# DriveBoard.net
KiCad netlist of a schematic drawn in Altium Designer
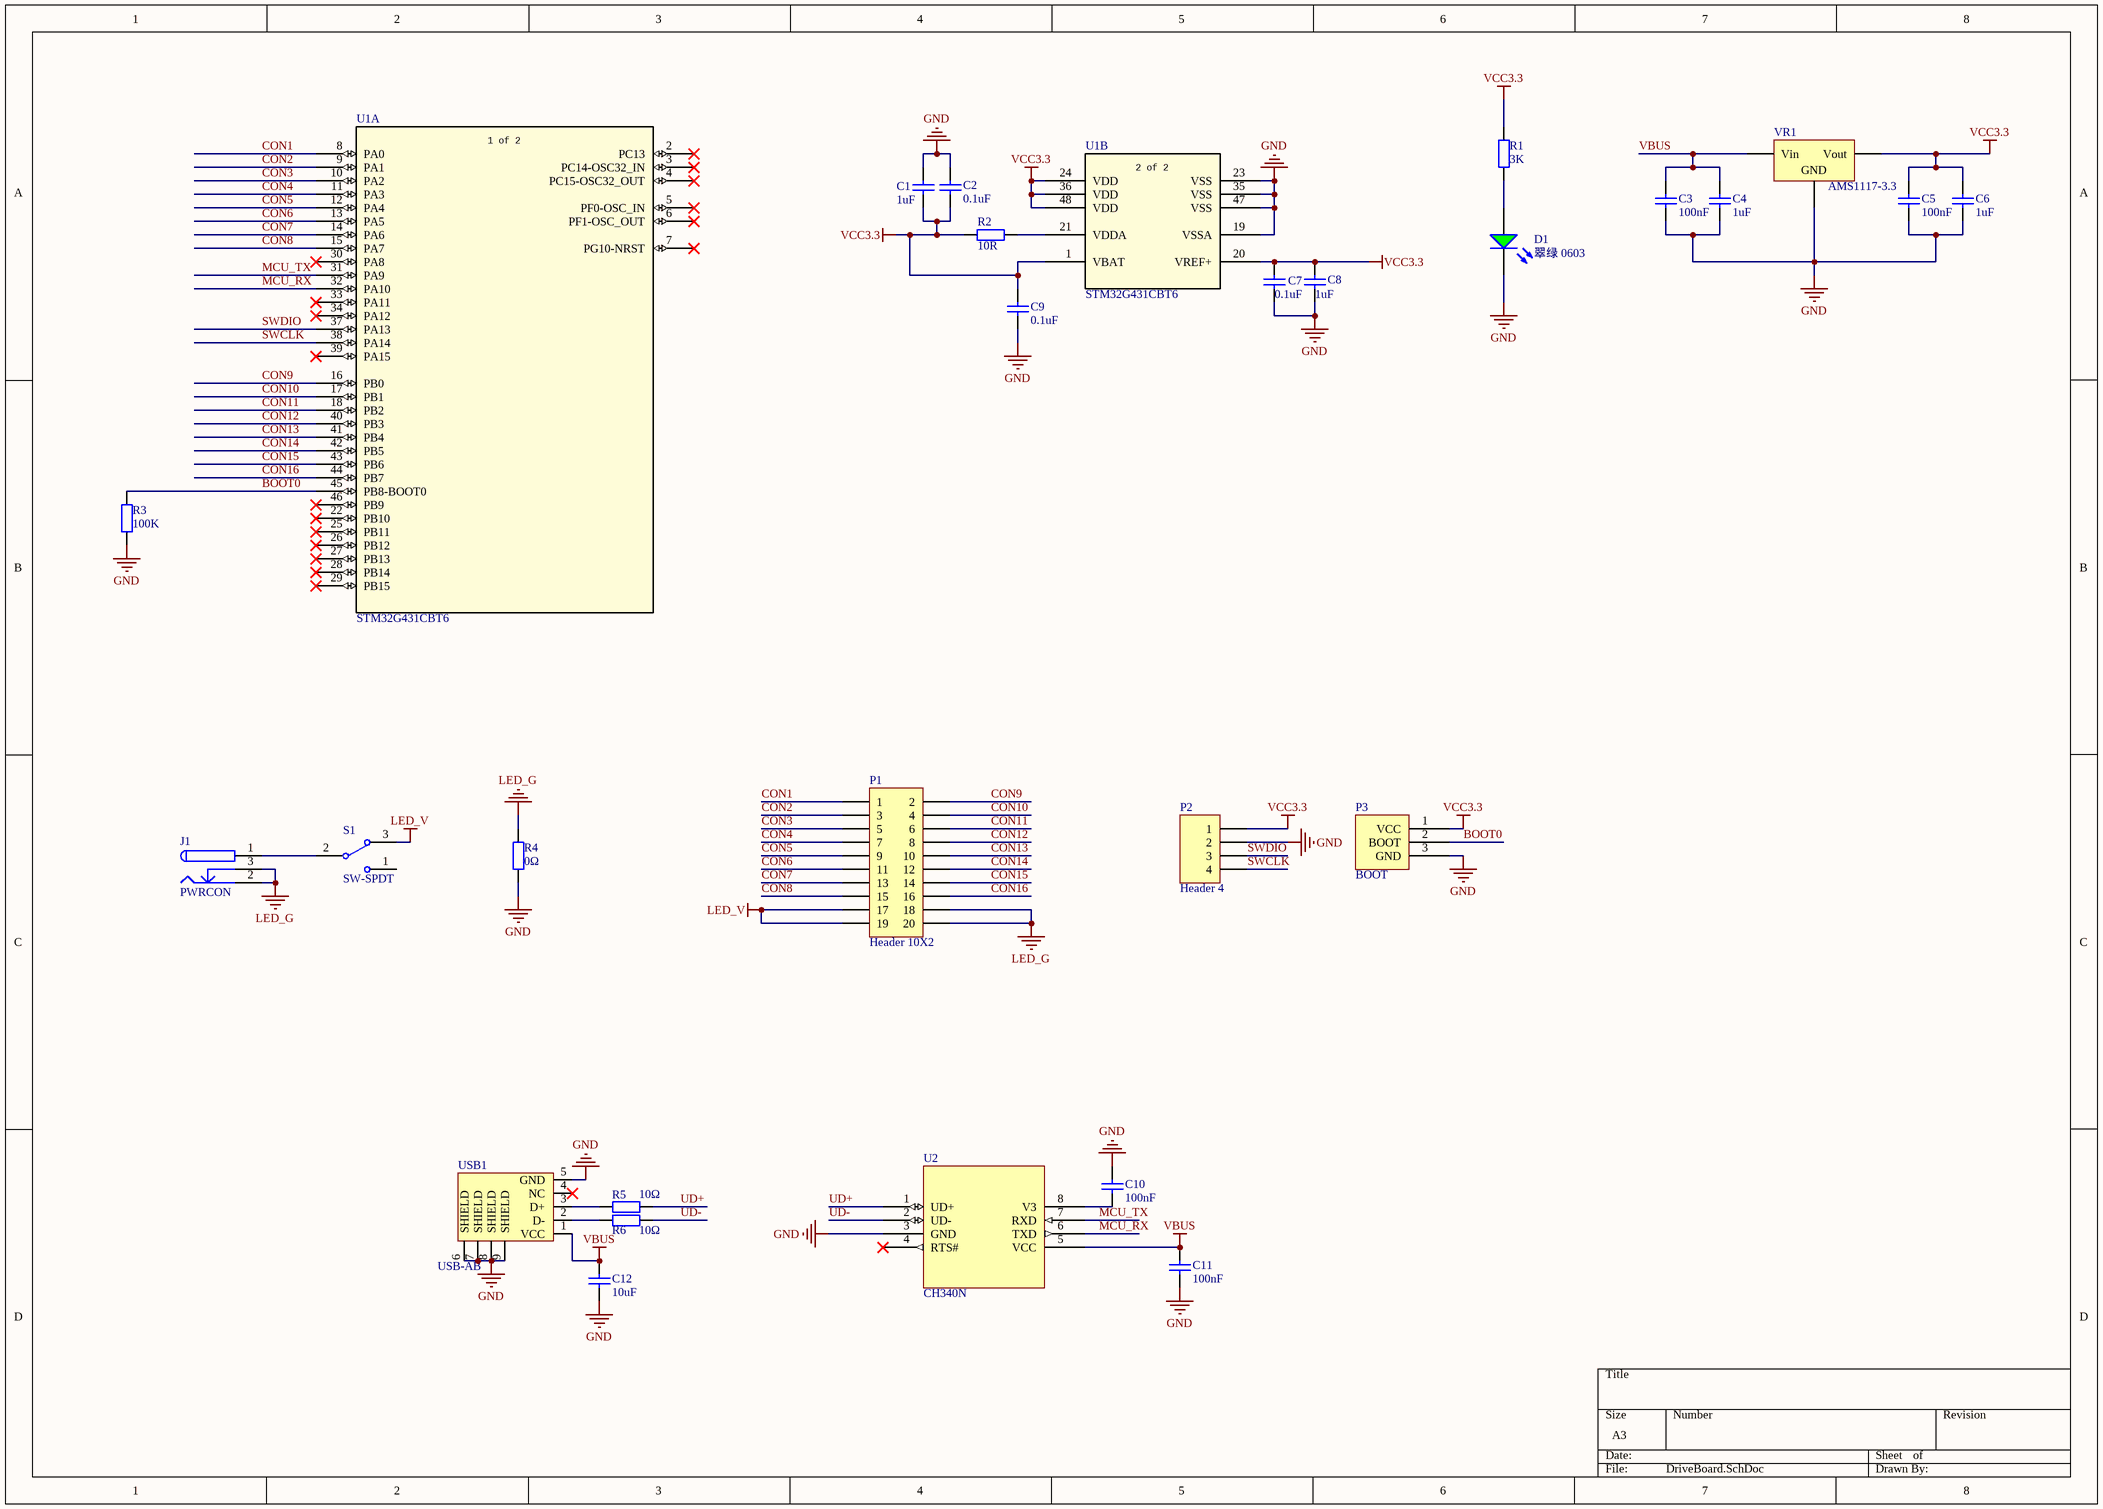
[diagram p0: DriveBoard.SchDoc]

(export (version "E")
  (design (tool "Eeschema 10.0.6"))
  (components
    (comp (ref "C1")
      (value "1uF")
      (footprint "0603_C")
      (description "贴片电容")
      (libsource (lib "Miscellaneous Devices LC") (part "0805 1uF (105) 10% 50V"))
    )
    (comp (ref "C2")
      (value "0.1uF")
      (footprint "0603_C")
      (description "贴片电容")
      (libsource (lib "Miscellaneous Devices LC") (part "0805 1uF (105) 10% 50V"))
    )
    (comp (ref "C3")
      (value "100nF")
      (footprint "0603_C")
      (description "贴片电容")
      (libsource (lib "Miscellaneous Devices LC") (part "0603 100nF (104) 10% 50V"))
    )
    (comp (ref "C4")
      (value "1uF")
      (footprint "0603_C")
      (description "贴片电容")
      (libsource (lib "Miscellaneous Devices LC") (part "0603 1uF (105) 10% 50V"))
    )
    (comp (ref "C5")
      (value "100nF")
      (footprint "0603_C")
      (description "贴片电容")
      (libsource (lib "Miscellaneous Devices LC") (part "0603 100nF (104) 10% 50V"))
    )
    (comp (ref "C6")
      (value "1uF")
      (footprint "0603_C")
      (description "贴片电容")
      (libsource (lib "Miscellaneous Devices LC") (part "0603 1uF (105) 10% 50V"))
    )
    (comp (ref "C7")
      (value "0.1uF")
      (footprint "0603_C")
      (description "贴片电容")
      (libsource (lib "Miscellaneous Devices LC") (part "0805 1uF (105) 10% 50V"))
    )
    (comp (ref "C8")
      (value "1uF")
      (footprint "0603_C")
      (description "贴片电容")
      (libsource (lib "Miscellaneous Devices LC") (part "0805 1uF (105) 10% 50V"))
    )
    (comp (ref "C9")
      (value "0.1uF")
      (footprint "0603_C")
      (description "贴片电容")
      (libsource (lib "Miscellaneous Devices LC") (part "0805 1uF (105) 10% 50V"))
    )
    (comp (ref "C10")
      (value "100nF")
      (footprint "0603_C")
      (description "贴片电容")
      (libsource (lib "Miscellaneous Devices LC") (part "0603 100nF (104) 10% 50V"))
    )
    (comp (ref "C11")
      (value "100nF")
      (footprint "0603_C")
      (description "贴片电容")
      (libsource (lib "Miscellaneous Devices LC") (part "0603 100nF (104) 10% 50V"))
    )
    (comp (ref "C12")
      (value "10uF")
      (footprint "0603_C")
      (description "贴片电容")
      (libsource (lib "Miscellaneous Devices LC") (part "0603 100nF (104) 10% 50V"))
    )
    (comp (ref "D1")
      (value "翠绿 0603")
      (footprint "0603_LED_S1")
      (description "发光二极管")
      (libsource (lib "Miscellaneous Devices LC") (part "0805 翠绿"))
    )
    (comp (ref "J1")
      (value "PWRCON")
      (footprint "Connetor:DC-005")
      (description "直流电源端子")
      (fields (field (name "PUBLISHER") "Altium Limited"))
      (libsource (lib "myself") (part "PWRCON"))
    )
    (comp (ref "P1")
      (value "Header 10X2")
      (footprint "HDR2.54-M-LS-2x10P")
      (description "Header, 10-Pin, Dual row")
      (fields (field (name "PUBLISHER") "Altium Limited"))
      (libsource (lib "Miscellaneous Connectors") (part "Header 10X2"))
    )
    (comp (ref "P2")
      (value "Header 4")
      (footprint "HDR1X4")
      (description "Header, 4-Pin")
      (fields (field (name "PUBLISHER") "Altium Limited"))
      (libsource (lib "Miscellaneous Connectors") (part "Header 4"))
    )
    (comp (ref "P3") (value "BOOT") (footprint "BOOT") (libsource (lib "myself") (part "BOOT")))
    (comp (ref "R1")
      (value "3K")
      (footprint "0603_R")
      (description "贴片电阻")
      (libsource (lib "Miscellaneous Devices LC") (part "0805 9.1KΩ (9101) 1%"))
    )
    (comp (ref "R2")
      (value "10R")
      (footprint "0603_R")
      (description "贴片电阻")
      (libsource (lib "Miscellaneous Devices LC") (part "0805 9.1KΩ (9101) 1%"))
    )
    (comp (ref "R3")
      (value "100K")
      (footprint "0603_R")
      (description "贴片电阻")
      (libsource (lib "") (part "0805 9.1KΩ (9101) 1%_1"))
    )
    (comp (ref "R4")
      (value "0Ω")
      (footprint "LC-0603_R")
      (description "贴片电阻")
      (libsource (lib "sfzself") (part "0603 0Ω (0R0) 1%"))
    )
    (comp (ref "R5")
      (value "10Ω")
      (footprint "0603_R")
      (description "贴片电阻")
      (libsource (lib "Miscellaneous Devices LC") (part "0603 10Ω (10R0) 1%"))
    )
    (comp (ref "R6")
      (value "10Ω")
      (footprint "0603_R")
      (description "贴片电阻")
      (libsource (lib "Miscellaneous Devices LC") (part "0603 10Ω (10R0) 1%"))
    )
    (comp (ref "S1")
      (value "SW-SPDT")
      (footprint "SWITCH_A1")
      (description "开关")
      (fields (field (name "PUBLISHER") "Altium Limited"))
      (libsource (lib "Fszhang") (part "SW-SPDT"))
    )
    (comp (ref "U1")
      (value "STM32G431CBT6")
      (footprint "LQFP48-7x7mm")
      (description "No Description Available")
      (fields (field (name "COPYRIGHT") "Copyright (C) 2018 Accelerated Designs. All rights reserved"))
      (libsource (lib "myself") (part "STM32G431CBT6"))
    )
    (comp (ref "U2")
      (value "CH340N")
      (footprint "SOP8")
      (description "USB to TTL Serial / UART")
      (libsource (lib "myself") (part "CH340N"))
    )
    (comp (ref "USB1")
      (value "USB-AB")
      (footprint "USB_AB - 5S - B")
      (description "MicroUSB")
      (libsource (lib "myself") (part "USB-AB"))
    )
    (comp (ref "VR1")
      (value "AMS1117-3.3")
      (footprint "SOT-223")
      (description "低压差线性稳压(LDO)")
      (libsource (lib "Miscellaneous Devices LC") (part "SOT-223 AMS1117-3.3"))
    )
  )
  (nets
    (net (code "1") (name "/BOOT0") (class "Default")
      (node (ref "P3") (pin "2") (pinfunction "BOOT_2") (pintype "passive"))
      (node (ref "R3") (pin "1") (pinfunction "1_1") (pintype "passive"))
      (node (ref "U1") (pin "45") (pinfunction "PB8-BOOT0_45") (pintype "bidirectional"))
    )
    (net (code "2") (name "/CON1") (class "Default")
      (node (ref "P1") (pin "1") (pinfunction "1_1") (pintype "passive"))
      (node (ref "U1") (pin "8") (pinfunction "PA0_8") (pintype "bidirectional"))
    )
    (net (code "3") (name "/CON2") (class "Default")
      (node (ref "P1") (pin "3") (pinfunction "3_3") (pintype "passive"))
      (node (ref "U1") (pin "9") (pinfunction "PA1_9") (pintype "bidirectional"))
    )
    (net (code "4") (name "/CON3") (class "Default")
      (node (ref "P1") (pin "5") (pinfunction "5_5") (pintype "passive"))
      (node (ref "U1") (pin "10") (pinfunction "PA2_10") (pintype "bidirectional"))
    )
    (net (code "5") (name "/CON4") (class "Default")
      (node (ref "P1") (pin "7") (pinfunction "7_7") (pintype "passive"))
      (node (ref "U1") (pin "11") (pinfunction "PA3_11") (pintype "bidirectional"))
    )
    (net (code "6") (name "/CON5") (class "Default")
      (node (ref "P1") (pin "9") (pinfunction "9_9") (pintype "passive"))
      (node (ref "U1") (pin "12") (pinfunction "PA4_12") (pintype "bidirectional"))
    )
    (net (code "7") (name "/CON6") (class "Default")
      (node (ref "P1") (pin "11") (pinfunction "11_11") (pintype "passive"))
      (node (ref "U1") (pin "13") (pinfunction "PA5_13") (pintype "bidirectional"))
    )
    (net (code "8") (name "/CON7") (class "Default")
      (node (ref "P1") (pin "13") (pinfunction "13_13") (pintype "passive"))
      (node (ref "U1") (pin "14") (pinfunction "PA6_14") (pintype "bidirectional"))
    )
    (net (code "9") (name "/CON8") (class "Default")
      (node (ref "P1") (pin "15") (pinfunction "15_15") (pintype "passive"))
      (node (ref "U1") (pin "15") (pinfunction "PA7_15") (pintype "bidirectional"))
    )
    (net (code "10") (name "/CON9") (class "Default")
      (node (ref "P1") (pin "2") (pinfunction "2_2") (pintype "passive"))
      (node (ref "U1") (pin "16") (pinfunction "PB0_16") (pintype "bidirectional"))
    )
    (net (code "11") (name "/CON10") (class "Default")
      (node (ref "P1") (pin "4") (pinfunction "4_4") (pintype "passive"))
      (node (ref "U1") (pin "17") (pinfunction "PB1_17") (pintype "bidirectional"))
    )
    (net (code "12") (name "/CON11") (class "Default")
      (node (ref "P1") (pin "6") (pinfunction "6_6") (pintype "passive"))
      (node (ref "U1") (pin "18") (pinfunction "PB2_18") (pintype "bidirectional"))
    )
    (net (code "13") (name "/CON12") (class "Default")
      (node (ref "P1") (pin "8") (pinfunction "8_8") (pintype "passive"))
      (node (ref "U1") (pin "40") (pinfunction "PB3_40") (pintype "bidirectional"))
    )
    (net (code "14") (name "/CON13") (class "Default")
      (node (ref "P1") (pin "10") (pinfunction "10_10") (pintype "passive"))
      (node (ref "U1") (pin "41") (pinfunction "PB4_41") (pintype "bidirectional"))
    )
    (net (code "15") (name "/CON14") (class "Default")
      (node (ref "P1") (pin "12") (pinfunction "12_12") (pintype "passive"))
      (node (ref "U1") (pin "42") (pinfunction "PB5_42") (pintype "bidirectional"))
    )
    (net (code "16") (name "/CON15") (class "Default")
      (node (ref "P1") (pin "14") (pinfunction "14_14") (pintype "passive"))
      (node (ref "U1") (pin "43") (pinfunction "PB6_43") (pintype "bidirectional"))
    )
    (net (code "17") (name "/CON16") (class "Default")
      (node (ref "P1") (pin "16") (pinfunction "16_16") (pintype "passive"))
      (node (ref "U1") (pin "44") (pinfunction "PB7_44") (pintype "bidirectional"))
    )
    (net (code "18") (name "/MCU_RX") (class "Default")
      (node (ref "U1") (pin "32") (pinfunction "PA10_32") (pintype "bidirectional"))
      (node (ref "U2") (pin "6") (pinfunction "TXD_6") (pintype "output"))
    )
    (net (code "19") (name "/MCU_TX") (class "Default")
      (node (ref "U1") (pin "31") (pinfunction "PA9_31") (pintype "bidirectional"))
      (node (ref "U2") (pin "7") (pinfunction "RXD_7") (pintype "input"))
    )
    (net (code "20") (name "/SWCLK") (class "Default")
      (node (ref "P2") (pin "4") (pinfunction "4_4") (pintype "passive"))
      (node (ref "U1") (pin "38") (pinfunction "PA14_38") (pintype "bidirectional"))
    )
    (net (code "21") (name "/SWDIO") (class "Default")
      (node (ref "P2") (pin "3") (pinfunction "3_3") (pintype "passive"))
      (node (ref "U1") (pin "37") (pinfunction "PA13_37") (pintype "bidirectional"))
    )
    (net (code "22") (name "/UD+") (class "Default")
      (node (ref "R5") (pin "2") (pinfunction "2_2") (pintype "passive"))
      (node (ref "U2") (pin "1") (pinfunction "UD+_1") (pintype "bidirectional"))
    )
    (net (code "23") (name "/UD-") (class "Default")
      (node (ref "R6") (pin "2") (pinfunction "2_2") (pintype "passive"))
      (node (ref "U2") (pin "2") (pinfunction "UD-_2") (pintype "bidirectional"))
    )
    (net (code "24") (name "GND") (class "Default")
      (node (ref "C1") (pin "1") (pinfunction "1_1") (pintype "passive"))
      (node (ref "C10") (pin "2") (pinfunction "2_2") (pintype "passive"))
      (node (ref "C11") (pin "1") (pinfunction "1_1") (pintype "passive"))
      (node (ref "C12") (pin "1") (pinfunction "1_1") (pintype "passive"))
      (node (ref "C2") (pin "1") (pinfunction "1_1") (pintype "passive"))
      (node (ref "C3") (pin "1") (pinfunction "1_1") (pintype "passive"))
      (node (ref "C4") (pin "1") (pinfunction "1_1") (pintype "passive"))
      (node (ref "C5") (pin "1") (pinfunction "1_1") (pintype "passive"))
      (node (ref "C6") (pin "1") (pinfunction "1_1") (pintype "passive"))
      (node (ref "C7") (pin "1") (pinfunction "1_1") (pintype "passive"))
      (node (ref "C8") (pin "1") (pinfunction "1_1") (pintype "passive"))
      (node (ref "C9") (pin "2") (pinfunction "2_2") (pintype "passive"))
      (node (ref "D1") (pin "K") (pinfunction "K_K") (pintype "passive"))
      (node (ref "P2") (pin "2") (pinfunction "2_2") (pintype "passive"))
      (node (ref "P3") (pin "3") (pinfunction "GND_3") (pintype "passive"))
      (node (ref "R3") (pin "2") (pinfunction "2_2") (pintype "passive"))
      (node (ref "R4") (pin "2") (pinfunction "2_2") (pintype "passive"))
      (node (ref "U1") (pin "19") (pinfunction "VSSA_19") (pintype "power_in"))
      (node (ref "U1") (pin "23") (pinfunction "VSS_23") (pintype "power_in"))
      (node (ref "U1") (pin "35") (pinfunction "VSS_35") (pintype "power_in"))
      (node (ref "U1") (pin "47") (pinfunction "VSS_47") (pintype "power_in"))
      (node (ref "U2") (pin "3") (pinfunction "GND_3") (pintype "power_in"))
      (node (ref "USB1") (pin "5") (pinfunction "GND_5") (pintype "passive"))
      (node (ref "USB1") (pin "6") (pinfunction "SHIELD_6") (pintype "passive"))
      (node (ref "USB1") (pin "7") (pinfunction "SHIELD_7") (pintype "passive"))
      (node (ref "USB1") (pin "8") (pinfunction "SHIELD_8") (pintype "passive"))
      (node (ref "USB1") (pin "9") (pinfunction "SHIELD_9") (pintype "passive"))
      (node (ref "VR1") (pin "1") (pinfunction "GND_1") (pintype "passive"))
    )
    (net (code "25") (name "LED_G") (class "Default")
      (node (ref "J1") (pin "2") (pinfunction "2_2") (pintype "power_in"))
      (node (ref "J1") (pin "3") (pinfunction "3_3") (pintype "power_in"))
      (node (ref "P1") (pin "18") (pinfunction "18_18") (pintype "passive"))
      (node (ref "P1") (pin "20") (pinfunction "20_20") (pintype "passive"))
      (node (ref "R4") (pin "1") (pinfunction "1_1") (pintype "passive"))
    )
    (net (code "26") (name "LED_V") (class "Default")
      (node (ref "P1") (pin "17") (pinfunction "17_17") (pintype "passive"))
      (node (ref "P1") (pin "19") (pinfunction "19_19") (pintype "passive"))
      (node (ref "S1") (pin "3") (pinfunction "3_3") (pintype "passive"))
    )
    (net (code "27") (name "Net-(D1-PadA)") (class "Default")
      (node (ref "D1") (pin "A") (pinfunction "A_A") (pintype "passive"))
      (node (ref "R1") (pin "2") (pinfunction "2_2") (pintype "passive"))
    )
    (net (code "28") (name "Net-(J1-Pad1)") (class "Default")
      (node (ref "J1") (pin "1") (pinfunction "1_1") (pintype "power_in"))
      (node (ref "S1") (pin "2") (pinfunction "2_2") (pintype "passive"))
    )
    (net (code "29") (name "Net-(U1B-VDDA)") (class "Default")
      (node (ref "R2") (pin "1") (pinfunction "1_1") (pintype "passive"))
      (node (ref "U1") (pin "21") (pinfunction "VDDA_21") (pintype "power_in"))
    )
    (net (code "30") (name "Net-(U2-V3)") (class "Default")
      (node (ref "C10") (pin "1") (pinfunction "1_1") (pintype "passive"))
      (node (ref "U2") (pin "8") (pinfunction "V3_8") (pintype "power_in"))
    )
    (net (code "31") (name "Net-(USB1-D+)") (class "Default")
      (node (ref "R5") (pin "1") (pinfunction "1_1") (pintype "passive"))
      (node (ref "USB1") (pin "3") (pinfunction "D+_3") (pintype "passive"))
    )
    (net (code "32") (name "Net-(USB1-D-)") (class "Default")
      (node (ref "R6") (pin "1") (pinfunction "1_1") (pintype "passive"))
      (node (ref "USB1") (pin "2") (pinfunction "D-_2") (pintype "passive"))
    )
    (net (code "33") (name "VBUS") (class "Default")
      (node (ref "C11") (pin "2") (pinfunction "2_2") (pintype "passive"))
      (node (ref "C12") (pin "2") (pinfunction "2_2") (pintype "passive"))
      (node (ref "C3") (pin "2") (pinfunction "2_2") (pintype "passive"))
      (node (ref "C4") (pin "2") (pinfunction "2_2") (pintype "passive"))
      (node (ref "U2") (pin "5") (pinfunction "VCC_5") (pintype "power_in"))
      (node (ref "USB1") (pin "1") (pinfunction "VCC_1") (pintype "passive"))
      (node (ref "VR1") (pin "3") (pinfunction "Vin_3") (pintype "passive"))
    )
    (net (code "34") (name "VCC3.3") (class "Default")
      (node (ref "C1") (pin "2") (pinfunction "2_2") (pintype "passive"))
      (node (ref "C2") (pin "2") (pinfunction "2_2") (pintype "passive"))
      (node (ref "C5") (pin "2") (pinfunction "2_2") (pintype "passive"))
      (node (ref "C6") (pin "2") (pinfunction "2_2") (pintype "passive"))
      (node (ref "C7") (pin "2") (pinfunction "2_2") (pintype "passive"))
      (node (ref "C8") (pin "2") (pinfunction "2_2") (pintype "passive"))
      (node (ref "C9") (pin "1") (pinfunction "1_1") (pintype "passive"))
      (node (ref "P2") (pin "1") (pinfunction "1_1") (pintype "passive"))
      (node (ref "P3") (pin "1") (pinfunction "VCC_1") (pintype "passive"))
      (node (ref "R1") (pin "1") (pinfunction "1_1") (pintype "passive"))
      (node (ref "R2") (pin "2") (pinfunction "2_2") (pintype "passive"))
      (node (ref "U1") (pin "1") (pinfunction "VBAT_1") (pintype "power_in"))
      (node (ref "U1") (pin "20") (pinfunction "VREF+_20") (pintype "power_in"))
      (node (ref "U1") (pin "24") (pinfunction "VDD_24") (pintype "power_in"))
      (node (ref "U1") (pin "36") (pinfunction "VDD_36") (pintype "power_in"))
      (node (ref "U1") (pin "48") (pinfunction "VDD_48") (pintype "power_in"))
      (node (ref "VR1") (pin "2") (pinfunction "Vout_2") (pintype "passive"))
    )
    (net (code "35") (name "unconnected-(S1-Pad1)") (class "Default")
      (node (ref "S1") (pin "1") (pinfunction "1_1") (pintype "passive"))
    )
    (net (code "36") (name "unconnected-(U1A-PA8-Pad30)") (class "Default")
      (node (ref "U1") (pin "30") (pinfunction "PA8_30") (pintype "bidirectional+no_connect"))
    )
    (net (code "37") (name "unconnected-(U1A-PA11-Pad33)") (class "Default")
      (node (ref "U1") (pin "33") (pinfunction "PA11_33") (pintype "bidirectional+no_connect"))
    )
    (net (code "38") (name "unconnected-(U1A-PA12-Pad34)") (class "Default")
      (node (ref "U1") (pin "34") (pinfunction "PA12_34") (pintype "bidirectional+no_connect"))
    )
    (net (code "39") (name "unconnected-(U1A-PA15-Pad39)") (class "Default")
      (node (ref "U1") (pin "39") (pinfunction "PA15_39") (pintype "bidirectional+no_connect"))
    )
    (net (code "40") (name "unconnected-(U1A-PB9-Pad46)") (class "Default")
      (node (ref "U1") (pin "46") (pinfunction "PB9_46") (pintype "bidirectional+no_connect"))
    )
    (net (code "41") (name "unconnected-(U1A-PB10-Pad22)") (class "Default")
      (node (ref "U1") (pin "22") (pinfunction "PB10_22") (pintype "bidirectional+no_connect"))
    )
    (net (code "42") (name "unconnected-(U1A-PB11-Pad25)") (class "Default")
      (node (ref "U1") (pin "25") (pinfunction "PB11_25") (pintype "bidirectional+no_connect"))
    )
    (net (code "43") (name "unconnected-(U1A-PB12-Pad26)") (class "Default")
      (node (ref "U1") (pin "26") (pinfunction "PB12_26") (pintype "bidirectional+no_connect"))
    )
    (net (code "44") (name "unconnected-(U1A-PB13-Pad27)") (class "Default")
      (node (ref "U1") (pin "27") (pinfunction "PB13_27") (pintype "bidirectional+no_connect"))
    )
    (net (code "45") (name "unconnected-(U1A-PB14-Pad28)") (class "Default")
      (node (ref "U1") (pin "28") (pinfunction "PB14_28") (pintype "bidirectional+no_connect"))
    )
    (net (code "46") (name "unconnected-(U1A-PB15-Pad29)") (class "Default")
      (node (ref "U1") (pin "29") (pinfunction "PB15_29") (pintype "bidirectional+no_connect"))
    )
    (net (code "47") (name "unconnected-(U1A-PC13-Pad2)") (class "Default")
      (node (ref "U1") (pin "2") (pinfunction "PC13_2") (pintype "bidirectional+no_connect"))
    )
    (net (code "48") (name "unconnected-(U1A-PC14-OSC32_IN-Pad3)") (class "Default")
      (node (ref "U1") (pin "3") (pinfunction "PC14-OSC32_IN_3") (pintype "bidirectional+no_connect"))
    )
    (net (code "49") (name "unconnected-(U1A-PC15-OSC32_OUT-Pad4)") (class "Default")
      (node (ref "U1") (pin "4") (pinfunction "PC15-OSC32_OUT_4") (pintype "bidirectional+no_connect"))
    )
    (net (code "50") (name "unconnected-(U1A-PF0-OSC_IN-Pad5)") (class "Default")
      (node (ref "U1") (pin "5") (pinfunction "PF0-OSC_IN_5") (pintype "bidirectional+no_connect"))
    )
    (net (code "51") (name "unconnected-(U1A-PF1-OSC_OUT-Pad6)") (class "Default")
      (node (ref "U1") (pin "6") (pinfunction "PF1-OSC_OUT_6") (pintype "bidirectional+no_connect"))
    )
    (net (code "52") (name "unconnected-(U1A-PG10-NRST-Pad7)") (class "Default")
      (node (ref "U1") (pin "7") (pinfunction "PG10-NRST_7") (pintype "bidirectional+no_connect"))
    )
    (net (code "53") (name "unconnected-(U2-RTS#-Pad4)") (class "Default")
      (node (ref "U2") (pin "4") (pinfunction "RTS#_4") (pintype "output+no_connect"))
    )
    (net (code "54") (name "unconnected-(USB1-NC-Pad4)") (class "Default")
      (node (ref "USB1") (pin "4") (pinfunction "NC_4") (pintype "passive+no_connect"))
    )
  )
)
